# Digital_light_sensor_v0_9b.net
KiCad netlist of a schematic drawn in EAGLE
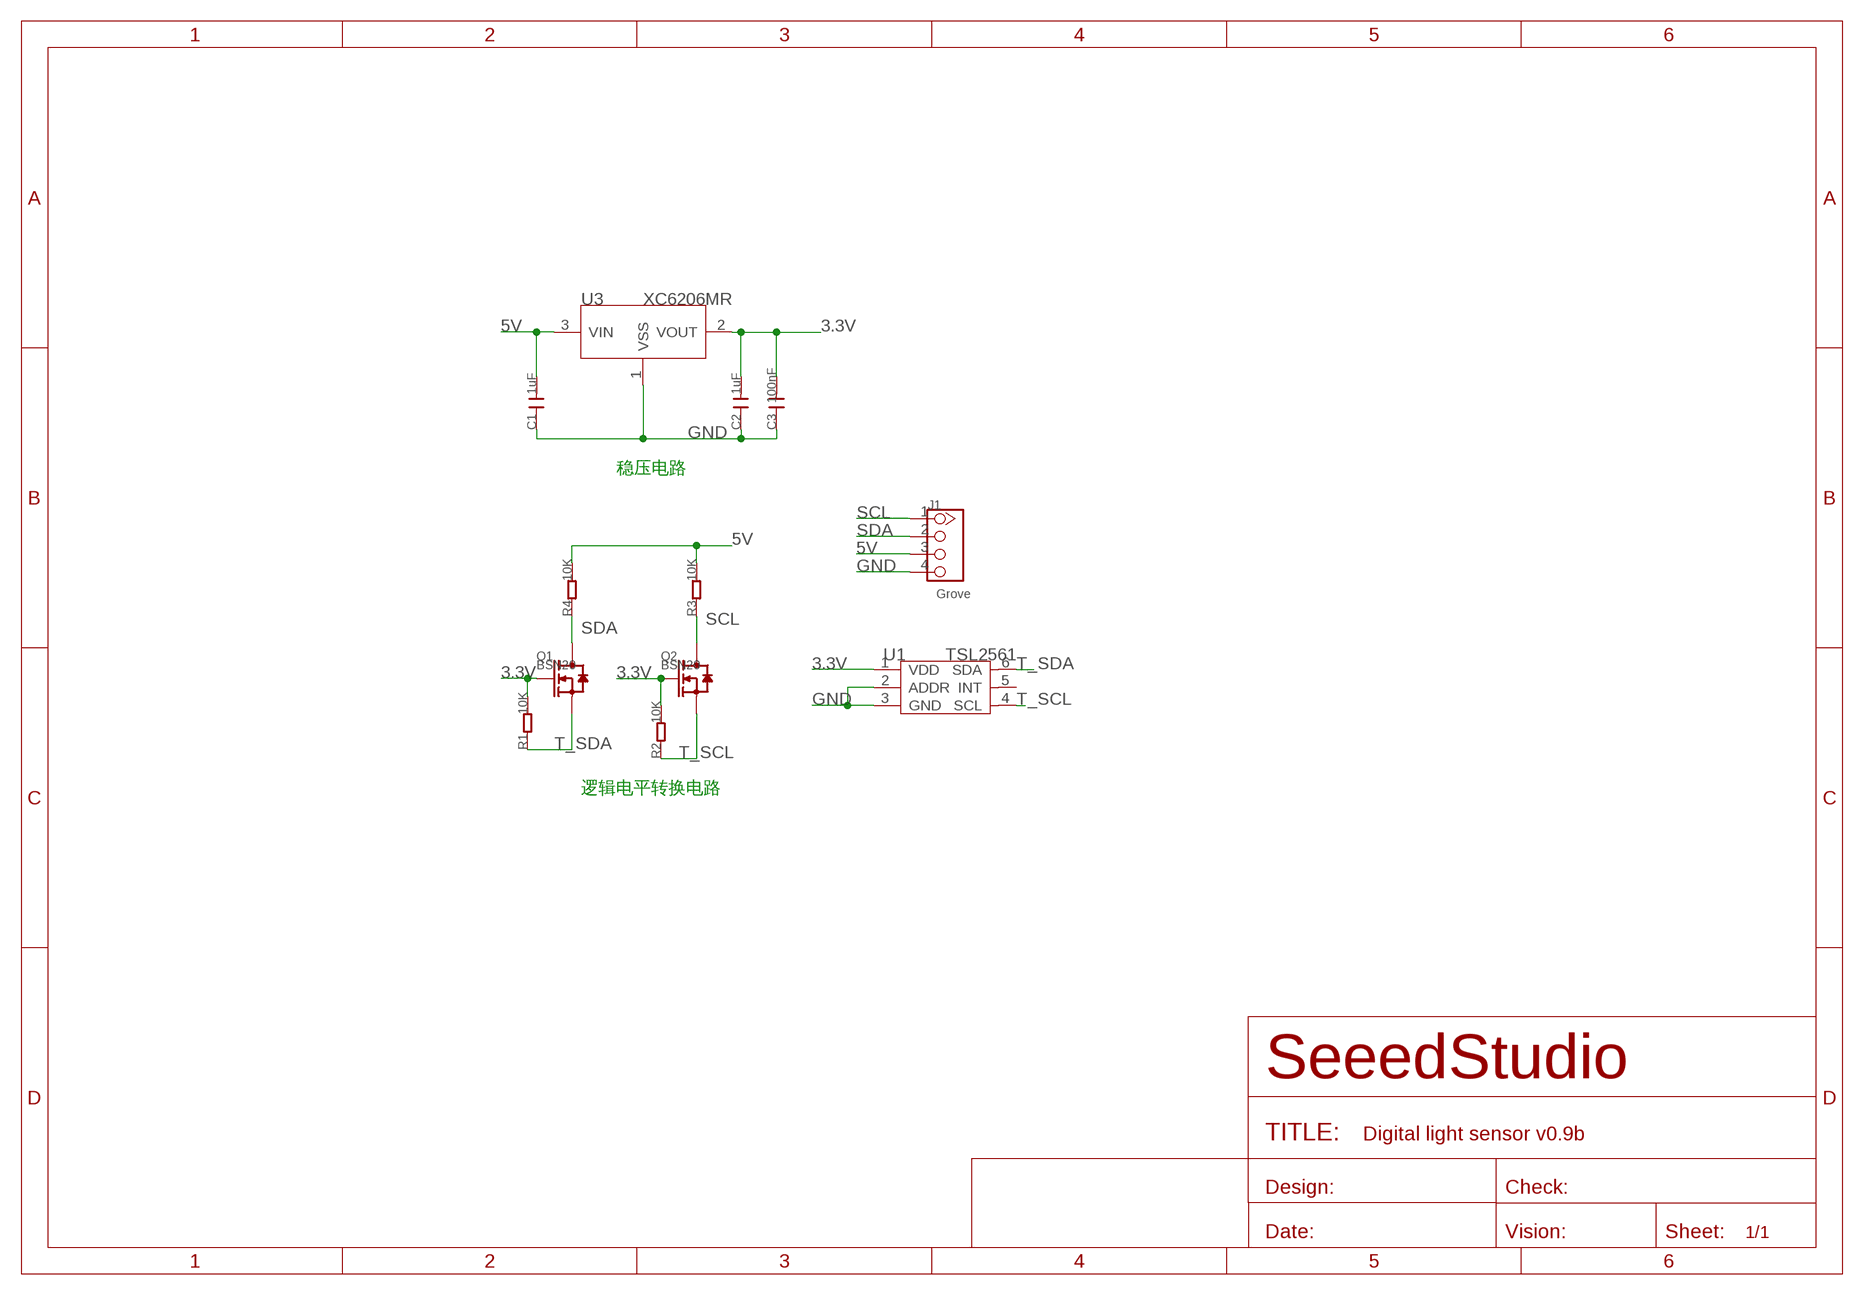
[diagram p0: schematic, sheet 1]

(export (version "E")
  (design (tool "Eeschema 10.0.6"))
  (components
    (comp (ref "C1")
      (value "1uF")
      (footprint "eagle-import:C0603")
      (libsource (lib "eagle-import") (part "C-0603"))
    )
    (comp (ref "C2")
      (value "1uF")
      (footprint "eagle-import:C0603")
      (libsource (lib "eagle-import") (part "C-0603"))
    )
    (comp (ref "C3")
      (value "100nF")
      (footprint "eagle-import:C0603")
      (libsource (lib "eagle-import") (part "C-0603"))
    )
    (comp (ref "J1")
      (value "Grove")
      (footprint "eagle-import:4P-2.0")
      (libsource (lib "eagle-import") (part "TWIG-4P-2.0-2.0"))
    )
    (comp (ref "Q1")
      (value "BSN20")
      (footprint "eagle-import:SOT23")
      (libsource (lib "eagle-import") (part "MOSFET-N'SOT23'"))
    )
    (comp (ref "Q2")
      (value "BSN20")
      (footprint "eagle-import:SOT23")
      (libsource (lib "eagle-import") (part "MOSFET-N'SOT23'"))
    )
    (comp (ref "R1")
      (value "10K")
      (footprint "eagle-import:R0603")
      (libsource (lib "eagle-import") (part "R-0603"))
    )
    (comp (ref "R2")
      (value "10K")
      (footprint "eagle-import:R0603")
      (libsource (lib "eagle-import") (part "R-0603"))
    )
    (comp (ref "R3")
      (value "10K")
      (footprint "eagle-import:R0603")
      (libsource (lib "eagle-import") (part "R-0603"))
    )
    (comp (ref "R4")
      (value "10K")
      (footprint "eagle-import:R0603")
      (libsource (lib "eagle-import") (part "R-0603"))
    )
    (comp (ref "U1")
      (value "TSL2561")
      (footprint "eagle-import:TMB-6")
      (libsource (lib "eagle-import") (part "TSL2561T"))
    )
    (comp (ref "U3")
      (value "XC6206MR")
      (footprint "eagle-import:SOT23")
      (libsource (lib "eagle-import") (part "XC6206MR"))
    )
  )
  (nets
    (net (code "1") (name "/3.3V") (class "Default")
      (node (ref "C2") (pin "2") (pinfunction "2_2") (pintype "passive"))
      (node (ref "C3") (pin "2") (pinfunction "2_2") (pintype "passive"))
      (node (ref "Q1") (pin "1") (pinfunction "G_1") (pintype "passive"))
      (node (ref "Q2") (pin "1") (pinfunction "G_1") (pintype "passive"))
      (node (ref "R1") (pin "2") (pinfunction "2_2") (pintype "passive"))
      (node (ref "R2") (pin "2") (pinfunction "2_2") (pintype "passive"))
      (node (ref "U1") (pin "1") (pinfunction "VDD_1") (pintype "power_in"))
      (node (ref "U3") (pin "2") (pinfunction "VOUT_2") (pintype "output"))
    )
    (net (code "2") (name "/5V") (class "Default")
      (node (ref "C1") (pin "2") (pinfunction "2_2") (pintype "passive"))
      (node (ref "J1") (pin "3") (pinfunction "3_3") (pintype "bidirectional"))
      (node (ref "R3") (pin "2") (pinfunction "2_2") (pintype "passive"))
      (node (ref "R4") (pin "2") (pinfunction "2_2") (pintype "passive"))
      (node (ref "U3") (pin "3") (pinfunction "VIN_3") (pintype "input"))
    )
    (net (code "3") (name "/GND") (class "Default")
      (node (ref "C1") (pin "1") (pinfunction "1_1") (pintype "passive"))
      (node (ref "C2") (pin "1") (pinfunction "1_1") (pintype "passive"))
      (node (ref "C3") (pin "1") (pinfunction "1_1") (pintype "passive"))
      (node (ref "J1") (pin "4") (pinfunction "4_4") (pintype "bidirectional"))
      (node (ref "U1") (pin "2") (pinfunction "ADDR_2") (pintype "input"))
      (node (ref "U1") (pin "3") (pinfunction "GND_3") (pintype "power_in"))
      (node (ref "U3") (pin "1") (pinfunction "VSS_1") (pintype "power_in"))
    )
    (net (code "4") (name "/SCL") (class "Default")
      (node (ref "J1") (pin "1") (pinfunction "1_1") (pintype "bidirectional"))
      (node (ref "Q2") (pin "3") (pinfunction "D_3") (pintype "passive"))
      (node (ref "R3") (pin "1") (pinfunction "1_1") (pintype "passive"))
    )
    (net (code "5") (name "/SDA") (class "Default")
      (node (ref "J1") (pin "2") (pinfunction "2_2") (pintype "bidirectional"))
      (node (ref "Q1") (pin "3") (pinfunction "D_3") (pintype "passive"))
      (node (ref "R4") (pin "1") (pinfunction "1_1") (pintype "passive"))
    )
    (net (code "6") (name "/T_SCL") (class "Default")
      (node (ref "Q2") (pin "2") (pinfunction "S_2") (pintype "passive"))
      (node (ref "R2") (pin "1") (pinfunction "1_1") (pintype "passive"))
      (node (ref "U1") (pin "4") (pinfunction "SCL_4") (pintype "input"))
    )
    (net (code "7") (name "/T_SDA") (class "Default")
      (node (ref "Q1") (pin "2") (pinfunction "S_2") (pintype "passive"))
      (node (ref "R1") (pin "1") (pinfunction "1_1") (pintype "passive"))
      (node (ref "U1") (pin "6") (pinfunction "SDA_6") (pintype "bidirectional"))
    )
    (net (code "8") (name "unconnected-(U1-INT-Pad5)") (class "Default")
      (node (ref "U1") (pin "5") (pinfunction "INT_5") (pintype "output"))
    )
  )
)
